# design.net
KiCad netlist of a schematic drawn in Altium Designer
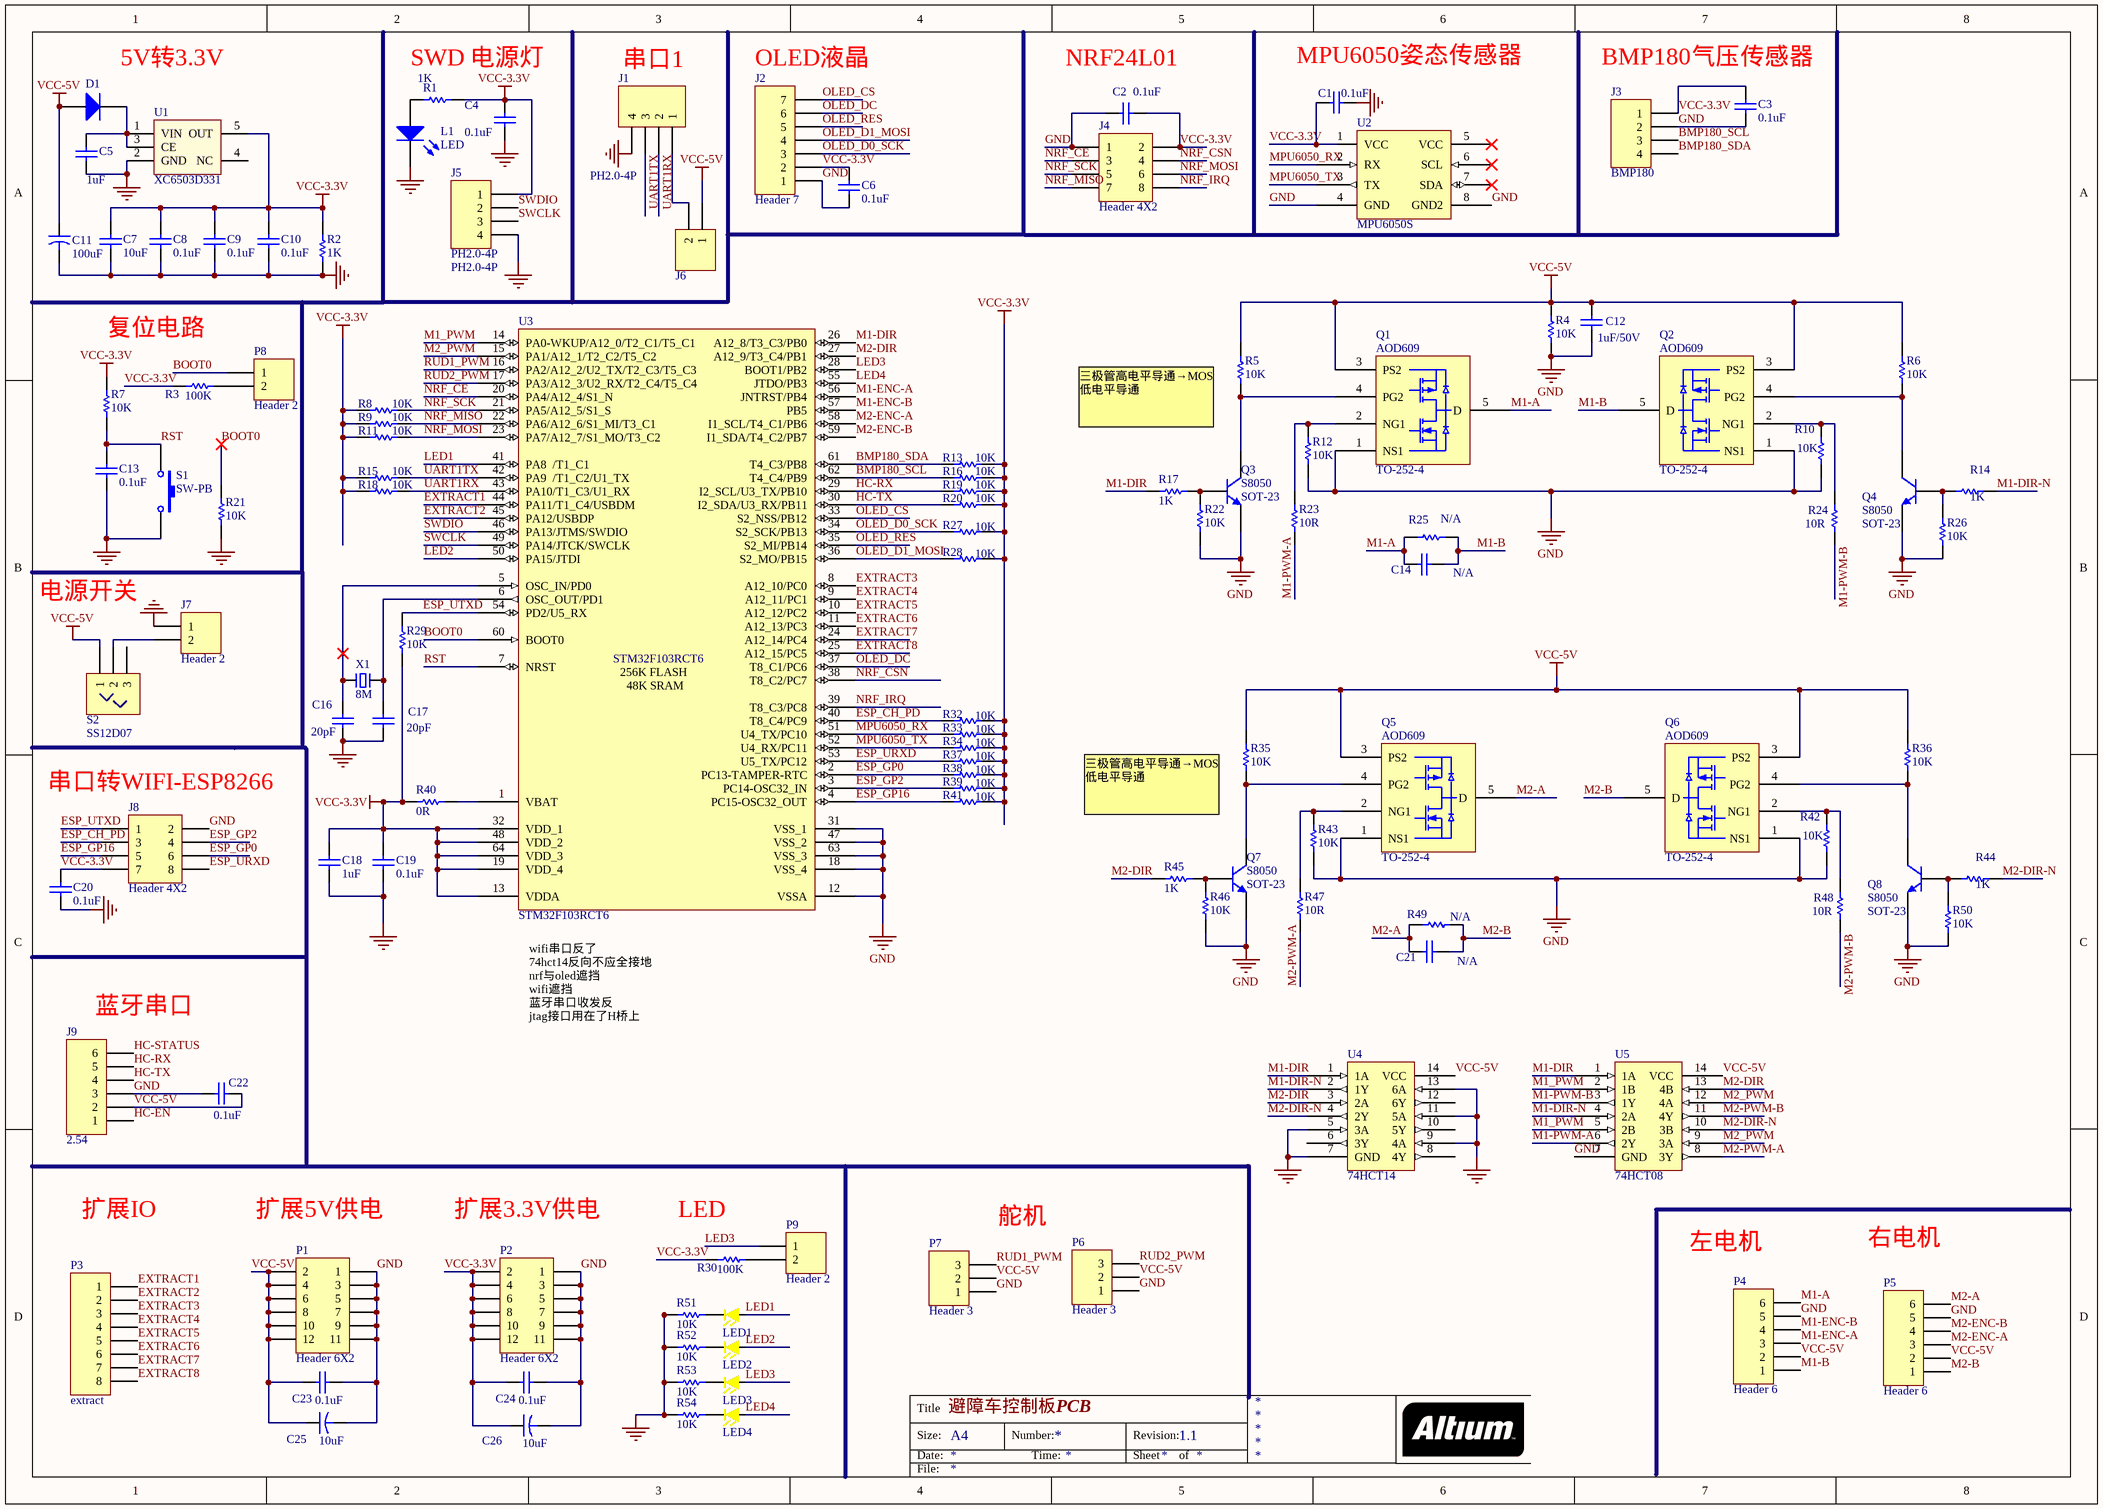
[diagram p0: 避障车控制板.SchDoc]

(export (version "E")
  (design (tool "Eeschema 10.0.6"))
  (components
    (comp (ref "C1")
      (value "0.1uF")
      (footprint "0805_LY")
      (description "Capacitor")
      (fields (field (name "PUBLISHER") "Altium Limited"))
      (libsource (lib "Miscellaneous Devices") (part "Cap"))
    )
    (comp (ref "C2")
      (value "0.1uF")
      (footprint "0805_LY")
      (description "Capacitor")
      (fields (field (name "PUBLISHER") "Altium Limited"))
      (libsource (lib "Miscellaneous Devices") (part "Cap"))
    )
    (comp (ref "C3")
      (value "0.1uF")
      (footprint "0805_LY")
      (description "电容0603")
      (fields (field (name "PUBLISHER") "Altium Limited"))
      (libsource (lib "Liyao原理图库") (part "Cap"))
    )
    (comp (ref "C4")
      (value "0.1uF")
      (footprint "0805_LY")
      (description "Capacitor")
      (fields (field (name "PUBLISHER") "Altium Limited"))
      (libsource (lib "Miscellaneous Devices") (part "Cap"))
    )
    (comp (ref "C5")
      (value "1uF")
      (footprint "0805_LY")
      (description "Capacitor")
      (fields (field (name "PUBLISHER") "Altium Limited"))
      (libsource (lib "Miscellaneous Devices") (part "Cap"))
    )
    (comp (ref "C6")
      (value "0.1uF")
      (footprint "0805_LY")
      (description "Capacitor")
      (fields (field (name "PUBLISHER") "Altium Limited"))
      (libsource (lib "Miscellaneous Devices") (part "Cap"))
    )
    (comp (ref "C7")
      (value "10uF")
      (footprint "0805_LY")
      (description "Capacitor")
      (fields (field (name "PUBLISHER") "Altium Limited"))
      (libsource (lib "Miscellaneous Devices") (part "Cap"))
    )
    (comp (ref "C8")
      (value "0.1uF")
      (footprint "0805_LY")
      (description "Capacitor")
      (fields (field (name "PUBLISHER") "Altium Limited"))
      (libsource (lib "Miscellaneous Devices") (part "Cap"))
    )
    (comp (ref "C9")
      (value "0.1uF")
      (footprint "0805_LY")
      (description "Capacitor")
      (fields (field (name "PUBLISHER") "Altium Limited"))
      (libsource (lib "Miscellaneous Devices") (part "Cap"))
    )
    (comp (ref "C10")
      (value "0.1uF")
      (footprint "0805_LY")
      (description "Capacitor")
      (fields (field (name "PUBLISHER") "Altium Limited"))
      (libsource (lib "Miscellaneous Devices") (part "Cap"))
    )
    (comp (ref "C11")
      (value "100uF")
      (footprint "TC6.3*7.7")
      (description "100uf/35v电解电容")
      (fields (field (name "PUBLISHER") "Altium Limited"))
      (libsource (lib "Liyao原理图库") (part "Cap100uf"))
    )
    (comp (ref "C12")
      (value "1uF/50V")
      (footprint "0805_LY")
      (description "Capacitor")
      (fields (field (name "PUBLISHER") "Altium Limited"))
      (libsource (lib "Miscellaneous Devices") (part "Cap"))
    )
    (comp (ref "C13")
      (value "0.1uF")
      (footprint "0805_LY")
      (description "Capacitor")
      (fields (field (name "PUBLISHER") "Altium Limited"))
      (libsource (lib "Miscellaneous Devices") (part "Cap"))
    )
    (comp (ref "C14")
      (value "N/A")
      (footprint "0805_LY")
      (description "Capacitor")
      (fields (field (name "PUBLISHER") "Altium Limited"))
      (libsource (lib "Miscellaneous Devices") (part "Cap"))
    )
    (comp (ref "C16")
      (value "20pF")
      (footprint "0805_LY")
      (description "Capacitor")
      (fields (field (name "PUBLISHER") "Altium Limited"))
      (libsource (lib "Miscellaneous Devices") (part "Cap"))
    )
    (comp (ref "C17")
      (value "20pF")
      (footprint "0805_LY")
      (description "Capacitor")
      (fields (field (name "PUBLISHER") "Altium Limited"))
      (libsource (lib "Miscellaneous Devices") (part "Cap"))
    )
    (comp (ref "C18")
      (value "1uF")
      (footprint "0805_LY")
      (description "Capacitor")
      (fields (field (name "PUBLISHER") "Altium Limited"))
      (libsource (lib "Miscellaneous Devices") (part "Cap"))
    )
    (comp (ref "C19")
      (value "0.1uF")
      (footprint "0805_LY")
      (description "Capacitor")
      (fields (field (name "PUBLISHER") "Altium Limited"))
      (libsource (lib "Miscellaneous Devices") (part "Cap"))
    )
    (comp (ref "C20")
      (value "0.1uF")
      (footprint "0805_LY")
      (description "Capacitor")
      (fields (field (name "PUBLISHER") "Altium Limited"))
      (libsource (lib "Miscellaneous Devices") (part "Cap"))
    )
    (comp (ref "C21")
      (value "N/A")
      (footprint "0805_LY")
      (description "Capacitor")
      (fields (field (name "PUBLISHER") "Altium Limited"))
      (libsource (lib "Miscellaneous Devices") (part "Cap"))
    )
    (comp (ref "C22")
      (value "0.1uF")
      (footprint "0805_LY")
      (description "Capacitor")
      (fields (field (name "PUBLISHER") "Altium Limited"))
      (libsource (lib "Miscellaneous Devices") (part "Cap"))
    )
    (comp (ref "C23")
      (value "0.1uF")
      (footprint "0805_LY")
      (description "电容0603")
      (fields (field (name "PUBLISHER") "Altium Limited"))
      (libsource (lib "Liyao原理图库") (part "Cap"))
    )
    (comp (ref "C24")
      (value "0.1uF")
      (footprint "0805_LY")
      (description "电容0603")
      (fields (field (name "PUBLISHER") "Altium Limited"))
      (libsource (lib "Liyao原理图库") (part "Cap"))
    )
    (comp (ref "C25")
      (value "10uF")
      (footprint "TC5*5")
      (description "10uf/35v电解电容")
      (fields (field (name "PUBLISHER") "Altium Limited"))
      (libsource (lib "Liyao原理图库") (part "Cap10uf"))
    )
    (comp (ref "C26")
      (value "10uF")
      (footprint "TC5*5")
      (description "10uf/35v电解电容")
      (fields (field (name "PUBLISHER") "Altium Limited"))
      (libsource (lib "Liyao原理图库") (part "Cap10uf"))
    )
    (comp (ref "D1")
      (value "SS14")
      (footprint "SMA")
      (description "28V 1A")
      (fields (field (name "PUBLISHER") "Altium Limited"))
      (libsource (lib "Liyao原理图库") (part "SS14"))
    )
    (comp (ref "J1")
      (value "PH2.0-4P")
      (footprint "XH2.54-4P")
      (description "插座XH2.54-4P")
      (fields (field (name "Comment") "XH2.54-4P") (field (name "PUBLISHER") "Altium Limited"))
      (libsource (lib "Liyao原理图库") (part "XH2.54-4P"))
    )
    (comp (ref "J2")
      (value "Header 7")
      (footprint "HDR1X7")
      (description "Header, 7-Pin")
      (fields (field (name "PUBLISHER") "Altium Limited"))
      (libsource (lib "Miscellaneous Connectors") (part "Header 7"))
    )
    (comp (ref "J3")
      (value "BMP180")
      (footprint "HDR1X4")
      (description "Header, 4-Pin")
      (fields (field (name "Comment") "PH2.0-4P") (field (name "PUBLISHER") "Altium Limited"))
      (libsource (lib "Miscellaneous Connectors") (part "Header 4"))
    )
    (comp (ref "J4")
      (value "Header 4X2")
      (footprint "HDR2X4")
      (description "Header, 4-Pin, Dual row")
      (fields (field (name "PUBLISHER") "Altium Limited"))
      (libsource (lib "Miscellaneous Connectors") (part "Header 4X2"))
    )
    (comp (ref "J5")
      (value "PH2.0-4P")
      (footprint "PH2.0-4P")
      (description "Header, 4-Pin")
      (fields (field (name "ALTIUM_VALUE") "PH2.0-4P") (field (name "PUBLISHER") "Altium Limited"))
      (libsource (lib "Miscellaneous Connectors") (part "Header 4"))
    )
    (comp (ref "J6")
      (value "XH2.54-2P")
      (footprint "CAP2.54-2P")
      (description "插座XH2.54-2P")
      (fields (field (name "PUBLISHER") "Altium Limited"))
      (libsource (lib "Liyao原理图库") (part "XH2.54-2P"))
    )
    (comp (ref "J7")
      (value "Header 2")
      (footprint "XH2.54-2P")
      (description "Header, 2-Pin")
      (fields (field (name "PUBLISHER") "Altium Limited"))
      (libsource (lib "Miscellaneous Connectors") (part "Header 2"))
    )
    (comp (ref "J8")
      (value "Header 4X2")
      (footprint "HDR2X4")
      (description "Header, 4-Pin, Dual row")
      (fields (field (name "PUBLISHER") "Altium Limited"))
      (libsource (lib "Miscellaneous Connectors") (part "Header 4X2"))
    )
    (comp (ref "J9")
      (value "2.54")
      (footprint "HDR1X6")
      (description "Header, 6-Pin")
      (fields (field (name "PUBLISHER") "Altium Limited"))
      (libsource (lib "Liyao端子库") (part "Header 6"))
    )
    (comp (ref "L1") (value "LED") (footprint "0805_LED") (libsource (lib "Sparks") (part "LED")))
    (comp (ref "LED1")
      (value "LED-Y")
      (footprint "0805_LED")
      (description "LED黄0603")
      (libsource (lib "Liyao原理图库") (part "LED-Y"))
    )
    (comp (ref "LED2")
      (value "LED-Y")
      (footprint "0805_LED")
      (description "LED黄0603")
      (libsource (lib "Liyao原理图库") (part "LED-Y"))
    )
    (comp (ref "LED3")
      (value "LED-Y")
      (footprint "0805_LED")
      (description "LED黄0603")
      (libsource (lib "Liyao原理图库") (part "LED-Y"))
    )
    (comp (ref "LED4")
      (value "LED-Y")
      (footprint "0805_LED")
      (description "LED黄0603")
      (libsource (lib "Liyao原理图库") (part "LED-Y"))
    )
    (comp (ref "P1")
      (value "Header 6X2")
      (footprint "HDR2X6")
      (description "Header, 6-Pin, Dual row")
      (fields (field (name "PUBLISHER") "Altium Limited"))
      (libsource (lib "Miscellaneous Connectors") (part "Header 6X2"))
    )
    (comp (ref "P2")
      (value "Header 6X2")
      (footprint "HDR2X6")
      (description "Header, 6-Pin, Dual row")
      (fields (field (name "PUBLISHER") "Altium Limited"))
      (libsource (lib "Miscellaneous Connectors") (part "Header 6X2"))
    )
    (comp (ref "P3")
      (value "extract")
      (footprint "HDR1X8")
      (description "Header, 8-Pin")
      (fields (field (name "PUBLISHER") "Altium Limited"))
      (libsource (lib "Miscellaneous Connectors") (part "Header 8"))
    )
    (comp (ref "P4")
      (value "Header 6")
      (footprint "PH2.0-6p")
      (description "Header, 6-Pin")
      (fields (field (name "PUBLISHER") "Altium Limited"))
      (libsource (lib "Miscellaneous Connectors") (part "Header 6"))
    )
    (comp (ref "P5")
      (value "Header 6")
      (footprint "PH2.0-6p")
      (description "Header, 6-Pin")
      (fields (field (name "PUBLISHER") "Altium Limited"))
      (libsource (lib "Miscellaneous Connectors") (part "Header 6"))
    )
    (comp (ref "P6")
      (value "Header 3")
      (footprint "HDR1X3")
      (description "Header, 3-Pin")
      (fields (field (name "PUBLISHER") "Altium Limited"))
      (libsource (lib "Miscellaneous Connectors") (part "Header 3"))
    )
    (comp (ref "P7")
      (value "Header 3")
      (footprint "HDR1X3")
      (description "Header, 3-Pin")
      (fields (field (name "PUBLISHER") "Altium Limited"))
      (libsource (lib "Miscellaneous Connectors") (part "Header 3"))
    )
    (comp (ref "P8")
      (value "Header 2")
      (footprint "HDR1X2")
      (description "Header, 2-Pin")
      (fields (field (name "PUBLISHER") "Altium Limited"))
      (libsource (lib "Liyao端子库") (part "Header 2"))
    )
    (comp (ref "P9")
      (value "Header 2")
      (footprint "HDR1X2")
      (description "Header, 2-Pin")
      (fields (field (name "PUBLISHER") "Altium Limited"))
      (libsource (lib "Liyao端子库") (part "Header 2"))
    )
    (comp (ref "Q1")
      (value "TO-252-4")
      (footprint "TO-252-4L")
      (fields (field (name "ALTIUM_VALUE") "AOD609"))
      (libsource (lib "CYSchlib") (part "MOS-DUAL-N/P"))
    )
    (comp (ref "Q2")
      (value "TO-252-4")
      (footprint "TO-252-4L")
      (fields (field (name "ALTIUM_VALUE") "AOD609"))
      (libsource (lib "") (part "MOS-DUAL-N/P_1"))
    )
    (comp (ref "Q3")
      (value "SOT-23")
      (footprint "SOT-23_L")
      (description "NPN Bipolar Transistor")
      (fields (field (name "ALTIUM_VALUE") "S8050") (field (name "PUBLISHER") "Altium Limited"))
      (libsource (lib "CYSchlib") (part "NPN"))
    )
    (comp (ref "Q4")
      (value "SOT-23")
      (footprint "SOT-23_L")
      (description "NPN Bipolar Transistor")
      (fields (field (name "ALTIUM_VALUE") "S8050") (field (name "PUBLISHER") "Altium Limited"))
      (libsource (lib "CYSchlib") (part "NPN"))
    )
    (comp (ref "Q5")
      (value "TO-252-4")
      (footprint "TO-252-4L")
      (fields (field (name "ALTIUM_VALUE") "AOD609"))
      (libsource (lib "CYSchlib") (part "MOS-DUAL-N/P"))
    )
    (comp (ref "Q6")
      (value "TO-252-4")
      (footprint "TO-252-4L")
      (fields (field (name "ALTIUM_VALUE") "AOD609"))
      (libsource (lib "") (part "MOS-DUAL-N/P_1"))
    )
    (comp (ref "Q7")
      (value "SOT-23")
      (footprint "SOT-23_L")
      (description "NPN Bipolar Transistor")
      (fields (field (name "ALTIUM_VALUE") "S8050") (field (name "PUBLISHER") "Altium Limited"))
      (libsource (lib "CYSchlib") (part "NPN"))
    )
    (comp (ref "Q8")
      (value "SOT-23")
      (footprint "SOT-23_L")
      (description "NPN Bipolar Transistor")
      (fields (field (name "ALTIUM_VALUE") "S8050") (field (name "PUBLISHER") "Altium Limited"))
      (libsource (lib "CYSchlib") (part "NPN"))
    )
    (comp (ref "R1")
      (value "1K")
      (footprint "0805_LY")
      (description "Resistor")
      (fields (field (name "PUBLISHER") "Altium Limited"))
      (libsource (lib "Miscellaneous Devices") (part "Res1"))
    )
    (comp (ref "R2")
      (value "1K")
      (footprint "0805_LY")
      (description "Resistor")
      (fields (field (name "PUBLISHER") "Altium Limited"))
      (libsource (lib "Miscellaneous Devices") (part "Res1"))
    )
    (comp (ref "R3")
      (value "100K")
      (footprint "6-0805_N")
      (description "电阻0603")
      (fields (field (name "PUBLISHER") "Altium Limited"))
      (libsource (lib "Liyao原理图库") (part "Res"))
    )
    (comp (ref "R4")
      (value "10K")
      (footprint "0805_LY")
      (description "Resistor")
      (fields (field (name "PUBLISHER") "Altium Limited"))
      (libsource (lib "Miscellaneous Devices") (part "Res1"))
    )
    (comp (ref "R5")
      (value "10K")
      (footprint "0805_LY")
      (description "Resistor")
      (fields (field (name "PUBLISHER") "Altium Limited"))
      (libsource (lib "Miscellaneous Devices") (part "Res1"))
    )
    (comp (ref "R6")
      (value "10K")
      (footprint "0805_LY")
      (description "Resistor")
      (fields (field (name "PUBLISHER") "Altium Limited"))
      (libsource (lib "Miscellaneous Devices") (part "Res1"))
    )
    (comp (ref "R7")
      (value "10K")
      (footprint "0805_LY")
      (description "Resistor")
      (fields (field (name "PUBLISHER") "Altium Limited"))
      (libsource (lib "Miscellaneous Devices") (part "Res1"))
    )
    (comp (ref "R8")
      (value "10K")
      (footprint "0805_LY")
      (description "电阻0603")
      (fields (field (name "PUBLISHER") "Altium Limited"))
      (libsource (lib "Liyao原理图库") (part "Res"))
    )
    (comp (ref "R9")
      (value "10K")
      (footprint "0805_LY")
      (description "电阻0603")
      (fields (field (name "PUBLISHER") "Altium Limited"))
      (libsource (lib "Liyao原理图库") (part "Res"))
    )
    (comp (ref "R10")
      (value "10K")
      (footprint "0805_LY")
      (description "Resistor")
      (fields (field (name "PUBLISHER") "Altium Limited"))
      (libsource (lib "Miscellaneous Devices") (part "Res1"))
    )
    (comp (ref "R11")
      (value "10K")
      (footprint "6-0805_N")
      (description "电阻0603")
      (fields (field (name "PUBLISHER") "Altium Limited"))
      (libsource (lib "Liyao原理图库") (part "Res"))
    )
    (comp (ref "R12")
      (value "10K")
      (footprint "0805_LY")
      (description "Resistor")
      (fields (field (name "PUBLISHER") "Altium Limited"))
      (libsource (lib "Miscellaneous Devices") (part "Res1"))
    )
    (comp (ref "R13")
      (value "10K")
      (footprint "0805_LY")
      (description "电阻0603")
      (fields (field (name "PUBLISHER") "Altium Limited"))
      (libsource (lib "Liyao原理图库") (part "Res"))
    )
    (comp (ref "R14")
      (value "1K")
      (footprint "0805_LY")
      (description "Resistor")
      (fields (field (name "PUBLISHER") "Altium Limited"))
      (libsource (lib "Miscellaneous Devices") (part "Res1"))
    )
    (comp (ref "R15")
      (value "10K")
      (footprint "0805_LY")
      (description "电阻0603")
      (fields (field (name "PUBLISHER") "Altium Limited"))
      (libsource (lib "Liyao原理图库") (part "Res"))
    )
    (comp (ref "R16")
      (value "10K")
      (footprint "0805_LY")
      (description "电阻0603")
      (fields (field (name "PUBLISHER") "Altium Limited"))
      (libsource (lib "Liyao原理图库") (part "Res"))
    )
    (comp (ref "R17")
      (value "1K")
      (footprint "0805_LY")
      (description "Resistor")
      (fields (field (name "PUBLISHER") "Altium Limited"))
      (libsource (lib "Miscellaneous Devices") (part "Res1"))
    )
    (comp (ref "R18")
      (value "10K")
      (footprint "0805_LY")
      (description "电阻0603")
      (fields (field (name "PUBLISHER") "Altium Limited"))
      (libsource (lib "Liyao原理图库") (part "Res"))
    )
    (comp (ref "R19")
      (value "10K")
      (footprint "0805_LY")
      (description "电阻0603")
      (fields (field (name "PUBLISHER") "Altium Limited"))
      (libsource (lib "Liyao原理图库") (part "Res"))
    )
    (comp (ref "R20")
      (value "10K")
      (footprint "0805_LY")
      (description "电阻0603")
      (fields (field (name "PUBLISHER") "Altium Limited"))
      (libsource (lib "Liyao原理图库") (part "Res"))
    )
    (comp (ref "R21")
      (value "10K")
      (footprint "0805_LY")
      (description "Resistor")
      (fields (field (name "PUBLISHER") "Altium Limited"))
      (libsource (lib "Miscellaneous Devices") (part "Res1"))
    )
    (comp (ref "R22")
      (value "10K")
      (footprint "0805_LY")
      (description "Resistor")
      (fields (field (name "PUBLISHER") "Altium Limited"))
      (libsource (lib "Miscellaneous Devices") (part "Res1"))
    )
    (comp (ref "R23")
      (value "10R")
      (footprint "0805_LY")
      (description "Resistor")
      (fields (field (name "PUBLISHER") "Altium Limited"))
      (libsource (lib "Miscellaneous Devices") (part "Res1"))
    )
    (comp (ref "R24")
      (value "10R")
      (footprint "0805_LY")
      (description "Resistor")
      (fields (field (name "PUBLISHER") "Altium Limited"))
      (libsource (lib "Miscellaneous Devices") (part "Res1"))
    )
    (comp (ref "R25")
      (value "N/A")
      (footprint "0805_LY")
      (description "Resistor")
      (fields (field (name "PUBLISHER") "Altium Limited"))
      (libsource (lib "Miscellaneous Devices") (part "Res1"))
    )
    (comp (ref "R26")
      (value "10K")
      (footprint "0805_LY")
      (description "Resistor")
      (fields (field (name "PUBLISHER") "Altium Limited"))
      (libsource (lib "Miscellaneous Devices") (part "Res1"))
    )
    (comp (ref "R27")
      (value "10K")
      (footprint "0805_LY")
      (description "电阻0603")
      (fields (field (name "PUBLISHER") "Altium Limited"))
      (libsource (lib "Liyao原理图库") (part "Res"))
    )
    (comp (ref "R28")
      (value "10K")
      (footprint "0805_LY")
      (description "电阻0603")
      (fields (field (name "PUBLISHER") "Altium Limited"))
      (libsource (lib "Liyao原理图库") (part "Res"))
    )
    (comp (ref "R29")
      (value "10K")
      (footprint "0805_LY")
      (description "电阻0603")
      (fields (field (name "PUBLISHER") "Altium Limited"))
      (libsource (lib "Liyao原理图库") (part "Res"))
    )
    (comp (ref "R30")
      (value "100K")
      (footprint "6-0805_N")
      (description "电阻0603")
      (fields (field (name "PUBLISHER") "Altium Limited"))
      (libsource (lib "Liyao原理图库") (part "Res"))
    )
    (comp (ref "R32")
      (value "10K")
      (footprint "0805_LY")
      (description "电阻0603")
      (fields (field (name "PUBLISHER") "Altium Limited"))
      (libsource (lib "Liyao原理图库") (part "Res"))
    )
    (comp (ref "R33")
      (value "10K")
      (footprint "0805_LY")
      (description "电阻0603")
      (fields (field (name "PUBLISHER") "Altium Limited"))
      (libsource (lib "Liyao原理图库") (part "Res"))
    )
    (comp (ref "R34")
      (value "10K")
      (footprint "0805_LY")
      (description "电阻0603")
      (fields (field (name "PUBLISHER") "Altium Limited"))
      (libsource (lib "Liyao原理图库") (part "Res"))
    )
    (comp (ref "R35")
      (value "10K")
      (footprint "0805_LY")
      (description "Resistor")
      (fields (field (name "PUBLISHER") "Altium Limited"))
      (libsource (lib "Miscellaneous Devices") (part "Res1"))
    )
    (comp (ref "R36")
      (value "10K")
      (footprint "0805_LY")
      (description "Resistor")
      (fields (field (name "PUBLISHER") "Altium Limited"))
      (libsource (lib "Miscellaneous Devices") (part "Res1"))
    )
    (comp (ref "R37")
      (value "10K")
      (footprint "0805_LY")
      (description "电阻0603")
      (fields (field (name "PUBLISHER") "Altium Limited"))
      (libsource (lib "Liyao原理图库") (part "Res"))
    )
    (comp (ref "R38")
      (value "10K")
      (footprint "0805_LY")
      (description "电阻0603")
      (fields (field (name "PUBLISHER") "Altium Limited"))
      (libsource (lib "Liyao原理图库") (part "Res"))
    )
    (comp (ref "R39")
      (value "10K")
      (footprint "0805_LY")
      (description "电阻0603")
      (fields (field (name "PUBLISHER") "Altium Limited"))
      (libsource (lib "Liyao原理图库") (part "Res"))
    )
    (comp (ref "R40")
      (value "0R")
      (footprint "0805_LY")
      (description "Resistor")
      (fields (field (name "PUBLISHER") "Altium Limited"))
      (libsource (lib "Miscellaneous Devices") (part "Res1"))
    )
    (comp (ref "R41")
      (value "10K")
      (footprint "0805_LY")
      (description "电阻0603")
      (fields (field (name "PUBLISHER") "Altium Limited"))
      (libsource (lib "Liyao原理图库") (part "Res"))
    )
    (comp (ref "R42")
      (value "10K")
      (footprint "0805_LY")
      (description "Resistor")
      (fields (field (name "PUBLISHER") "Altium Limited"))
      (libsource (lib "Miscellaneous Devices") (part "Res1"))
    )
    (comp (ref "R43")
      (value "10K")
      (footprint "0805_LY")
      (description "Resistor")
      (fields (field (name "PUBLISHER") "Altium Limited"))
      (libsource (lib "Miscellaneous Devices") (part "Res1"))
    )
    (comp (ref "R44")
      (value "1K")
      (footprint "0805_LY")
      (description "Resistor")
      (fields (field (name "PUBLISHER") "Altium Limited"))
      (libsource (lib "Miscellaneous Devices") (part "Res1"))
    )
    (comp (ref "R45")
      (value "1K")
      (footprint "0805_LY")
      (description "Resistor")
      (fields (field (name "PUBLISHER") "Altium Limited"))
      (libsource (lib "Miscellaneous Devices") (part "Res1"))
    )
    (comp (ref "R46")
      (value "10K")
      (footprint "0805_LY")
      (description "Resistor")
      (fields (field (name "PUBLISHER") "Altium Limited"))
      (libsource (lib "Miscellaneous Devices") (part "Res1"))
    )
    (comp (ref "R47")
      (value "10R")
      (footprint "0805_LY")
      (description "Resistor")
      (fields (field (name "PUBLISHER") "Altium Limited"))
      (libsource (lib "Miscellaneous Devices") (part "Res1"))
    )
    (comp (ref "R48")
      (value "10R")
      (footprint "0805_LY")
      (description "Resistor")
      (fields (field (name "PUBLISHER") "Altium Limited"))
      (libsource (lib "Miscellaneous Devices") (part "Res1"))
    )
    (comp (ref "R49")
      (value "N/A")
      (footprint "0805_LY")
      (description "Resistor")
      (fields (field (name "PUBLISHER") "Altium Limited"))
      (libsource (lib "Miscellaneous Devices") (part "Res1"))
    )
    (comp (ref "R50")
      (value "10K")
      (footprint "0805_LY")
      (description "Resistor")
      (fields (field (name "PUBLISHER") "Altium Limited"))
      (libsource (lib "Miscellaneous Devices") (part "Res1"))
    )
    (comp (ref "R51")
      (value "10K")
      (footprint "0805_LY")
      (description "电阻0603")
      (fields (field (name "PUBLISHER") "Altium Limited"))
      (libsource (lib "Liyao原理图库") (part "Res"))
    )
    (comp (ref "R52")
      (value "10K")
      (footprint "0805_LY")
      (description "电阻0603")
      (fields (field (name "PUBLISHER") "Altium Limited"))
      (libsource (lib "Liyao原理图库") (part "Res"))
    )
    (comp (ref "R53")
      (value "10K")
      (footprint "0805_LY")
      (description "电阻0603")
      (fields (field (name "PUBLISHER") "Altium Limited"))
      (libsource (lib "Liyao原理图库") (part "Res"))
    )
    (comp (ref "R54")
      (value "10K")
      (footprint "0805_LY")
      (description "电阻0603")
      (fields (field (name "PUBLISHER") "Altium Limited"))
      (libsource (lib "Liyao原理图库") (part "Res"))
    )
    (comp (ref "S1")
      (value "SW-PB")
      (footprint "SW-KEY")
      (description "Switch")
      (fields (field (name "PUBLISHER") "Altium Limited"))
      (libsource (lib "Miscellaneous Devices") (part "SW-PB"))
    )
    (comp (ref "S2") (value "SS12D07") (footprint "SS-12D07") (libsource (lib "Liyao原理图库") (part "SS12D07")))
    (comp (ref "U1")
      (value "XC6503D331")
      (footprint "SOT23-5")
      (libsource (lib "CYSchlib") (part "XC6503Dxxx"))
    )
    (comp (ref "U2")
      (value "MPU6050S")
      (footprint "MPU6050S")
      (libsource (lib "Liyao原理图库") (part "MPU6050S"))
    )
    (comp (ref "U3")
      (value "STM32F103RCT6")
      (footprint "LQFP64_N")
      (description "256K Flash 48K RAM")
      (fields (field (name "PUBLISHER") "Altium Limited"))
      (libsource (lib "Liyao原理图库") (part "STM32F103RCT6"))
    )
    (comp (ref "U4")
      (value "74HCT14")
      (footprint "SO-14")
      (description "反向输出 AL-YH,AH-YL")
      (libsource (lib "Liyao原理图库") (part "74HCT14"))
    )
    (comp (ref "U5")
      (value "74HCT08")
      (footprint "SO-14")
      (description "与门AH&&BH?YH:YL")
      (libsource (lib "Liyao原理图库") (part "74HCT08"))
    )
    (comp (ref "X1") (value "8M") (footprint "HC-49SMD") (libsource (lib "CYSchlib") (part "XTAL")))
  )
  (nets
    (net (code "1") (name "/BMP180_SCL") (class "Default")
      (node (ref "J3") (pin "3") (pinfunction "3_3") (pintype "passive"))
      (node (ref "R16") (pin "1") (pinfunction "1_1") (pintype "passive"))
      (node (ref "U3") (pin "62") (pinfunction "T4_C4/PB9_62") (pintype "bidirectional"))
    )
    (net (code "2") (name "/BMP180_SDA") (class "Default")
      (node (ref "J3") (pin "4") (pinfunction "4_4") (pintype "passive"))
      (node (ref "R13") (pin "1") (pinfunction "1_1") (pintype "passive"))
      (node (ref "U3") (pin "61") (pinfunction "T4_C3/PB8_61") (pintype "bidirectional"))
    )
    (net (code "3") (name "/BOOT0") (class "Default")
      (node (ref "P8") (pin "1") (pinfunction "1_1") (pintype "passive"))
      (node (ref "R21") (pin "1") (pinfunction "1_1") (pintype "passive"))
      (node (ref "U3") (pin "60") (pinfunction "BOOT0_60") (pintype "input"))
    )
    (net (code "4") (name "/ESP_CH_PD") (class "Default")
      (node (ref "J8") (pin "3") (pinfunction "3_3") (pintype "passive"))
      (node (ref "R32") (pin "1") (pinfunction "1_1") (pintype "passive"))
      (node (ref "U3") (pin "40") (pinfunction "T8_C4/PC9_40") (pintype "bidirectional"))
    )
    (net (code "5") (name "/ESP_GP0") (class "Default")
      (node (ref "J8") (pin "6") (pinfunction "6_6") (pintype "passive"))
      (node (ref "R38") (pin "1") (pinfunction "1_1") (pintype "passive"))
      (node (ref "U3") (pin "2") (pinfunction "PC13-TAMPER-RTC_2") (pintype "bidirectional"))
    )
    (net (code "6") (name "/ESP_GP2") (class "Default")
      (node (ref "J8") (pin "4") (pinfunction "4_4") (pintype "passive"))
      (node (ref "R39") (pin "1") (pinfunction "1_1") (pintype "passive"))
      (node (ref "U3") (pin "3") (pinfunction "PC14-OSC32_IN_3") (pintype "bidirectional"))
    )
    (net (code "7") (name "/ESP_GP16") (class "Default")
      (node (ref "J8") (pin "5") (pinfunction "5_5") (pintype "passive"))
      (node (ref "R41") (pin "1") (pinfunction "1_1") (pintype "passive"))
      (node (ref "U3") (pin "4") (pinfunction "PC15-OSC32_OUT_4") (pintype "bidirectional"))
    )
    (net (code "8") (name "/ESP_URXD") (class "Default")
      (node (ref "J8") (pin "8") (pinfunction "8_8") (pintype "passive"))
      (node (ref "R37") (pin "1") (pinfunction "1_1") (pintype "passive"))
      (node (ref "U3") (pin "53") (pinfunction "U5_TX/PC12_53") (pintype "bidirectional"))
    )
    (net (code "9") (name "/ESP_UTXD") (class "Default")
      (node (ref "J8") (pin "1") (pinfunction "1_1") (pintype "passive"))
      (node (ref "R29") (pin "2") (pinfunction "2_2") (pintype "passive"))
      (node (ref "U3") (pin "54") (pinfunction "PD2/U5_RX_54") (pintype "bidirectional"))
    )
    (net (code "10") (name "/EXTRACT1") (class "Default")
      (node (ref "P3") (pin "1") (pinfunction "1_1") (pintype "passive"))
      (node (ref "U3") (pin "44") (pinfunction "PA11/T1_C4/USBDM_44") (pintype "bidirectional"))
    )
    (net (code "11") (name "/EXTRACT2") (class "Default")
      (node (ref "P3") (pin "2") (pinfunction "2_2") (pintype "passive"))
      (node (ref "U3") (pin "45") (pinfunction "PA12/USBDP_45") (pintype "bidirectional"))
    )
    (net (code "12") (name "/EXTRACT3") (class "Default")
      (node (ref "P3") (pin "3") (pinfunction "3_3") (pintype "passive"))
      (node (ref "U3") (pin "8") (pinfunction "A12_10/PC0_8") (pintype "bidirectional"))
    )
    (net (code "13") (name "/EXTRACT4") (class "Default")
      (node (ref "P3") (pin "4") (pinfunction "4_4") (pintype "passive"))
      (node (ref "U3") (pin "9") (pinfunction "A12_11/PC1_9") (pintype "bidirectional"))
    )
    (net (code "14") (name "/EXTRACT5") (class "Default")
      (node (ref "P3") (pin "5") (pinfunction "5_5") (pintype "passive"))
      (node (ref "U3") (pin "10") (pinfunction "A12_12/PC2_10") (pintype "bidirectional"))
    )
    (net (code "15") (name "/EXTRACT6") (class "Default")
      (node (ref "P3") (pin "6") (pinfunction "6_6") (pintype "passive"))
      (node (ref "U3") (pin "11") (pinfunction "A12_13/PC3_11") (pintype "bidirectional"))
    )
    (net (code "16") (name "/EXTRACT7") (class "Default")
      (node (ref "P3") (pin "7") (pinfunction "7_7") (pintype "passive"))
      (node (ref "U3") (pin "24") (pinfunction "A12_14/PC4_24") (pintype "bidirectional"))
    )
    (net (code "17") (name "/EXTRACT8") (class "Default")
      (node (ref "P3") (pin "8") (pinfunction "8_8") (pintype "passive"))
      (node (ref "U3") (pin "25") (pinfunction "A12_15/PC5_25") (pintype "bidirectional"))
    )
    (net (code "18") (name "/HC-EN") (class "Default")
      (node (ref "J9") (pin "1") (pinfunction "1_1") (pintype "passive"))
    )
    (net (code "19") (name "/HC-RX") (class "Default")
      (node (ref "J9") (pin "5") (pinfunction "5_5") (pintype "passive"))
      (node (ref "R19") (pin "1") (pinfunction "1_1") (pintype "passive"))
      (node (ref "U3") (pin "29") (pinfunction "I2_SCL/U3_TX/PB10_29") (pintype "bidirectional"))
    )
    (net (code "20") (name "/HC-STATUS") (class "Default")
      (node (ref "J9") (pin "6") (pinfunction "6_6") (pintype "passive"))
    )
    (net (code "21") (name "/HC-TX") (class "Default")
      (node (ref "J9") (pin "4") (pinfunction "4_4") (pintype "passive"))
      (node (ref "R20") (pin "1") (pinfunction "1_1") (pintype "passive"))
      (node (ref "U3") (pin "30") (pinfunction "I2_SDA/U3_RX/PB11_30") (pintype "bidirectional"))
    )
    (net (code "22") (name "/LED1") (class "Default")
      (node (ref "LED1") (pin "1") (pinfunction "1_1") (pintype "passive"))
      (node (ref "U3") (pin "41") (pinfunction "PA8__/T1_C1_41") (pintype "bidirectional"))
    )
    (net (code "23") (name "/LED2") (class "Default")
      (node (ref "LED2") (pin "1") (pinfunction "1_1") (pintype "passive"))
      (node (ref "U3") (pin "50") (pinfunction "PA15/JTDI_50") (pintype "bidirectional"))
    )
    (net (code "24") (name "/LED3") (class "Default")
      (node (ref "LED3") (pin "1") (pinfunction "1_1") (pintype "passive"))
      (node (ref "P9") (pin "1") (pinfunction "1_1") (pintype "passive"))
      (node (ref "U3") (pin "28") (pinfunction "BOOT1/PB2_28") (pintype "bidirectional"))
    )
    (net (code "25") (name "/LED4") (class "Default")
      (node (ref "LED4") (pin "1") (pinfunction "1_1") (pintype "passive"))
      (node (ref "U3") (pin "55") (pinfunction "JTDO/PB3_55") (pintype "bidirectional"))
    )
    (net (code "26") (name "/M1-A") (class "Default")
      (node (ref "C14") (pin "2") (pinfunction "2_2") (pintype "passive"))
      (node (ref "P4") (pin "6") (pinfunction "6_6") (pintype "passive"))
      (node (ref "Q1") (pin "5") (pinfunction "D_5") (pintype "passive"))
      (node (ref "R25") (pin "2") (pinfunction "2_2") (pintype "passive"))
    )
    (net (code "27") (name "/M1-B") (class "Default")
      (node (ref "C14") (pin "1") (pinfunction "1_1") (pintype "passive"))
      (node (ref "P4") (pin "1") (pinfunction "1_1") (pintype "passive"))
      (node (ref "Q2") (pin "5") (pinfunction "D_5") (pintype "passive"))
      (node (ref "R25") (pin "1") (pinfunction "1_1") (pintype "passive"))
    )
    (net (code "28") (name "/M1-DIR") (class "Default")
      (node (ref "R17") (pin "2") (pinfunction "2_2") (pintype "passive"))
      (node (ref "U3") (pin "26") (pinfunction "A12_8/T3_C3/PB0_26") (pintype "bidirectional"))
      (node (ref "U4") (pin "1") (pinfunction "1A_1") (pintype "input"))
      (node (ref "U5") (pin "1") (pinfunction "1A_1") (pintype "input"))
    )
    (net (code "29") (name "/M1-DIR-N") (class "Default")
      (node (ref "R14") (pin "1") (pinfunction "1_1") (pintype "passive"))
      (node (ref "U4") (pin "2") (pinfunction "1Y_2") (pintype "output"))
      (node (ref "U5") (pin "4") (pinfunction "2A_4") (pintype "input"))
    )
    (net (code "30") (name "/M1-ENC-A") (class "Default")
      (node (ref "P4") (pin "3") (pinfunction "3_3") (pintype "passive"))
      (node (ref "U3") (pin "56") (pinfunction "JNTRST/PB4_56") (pintype "bidirectional"))
    )
    (net (code "31") (name "/M1-ENC-B") (class "Default")
      (node (ref "P4") (pin "4") (pinfunction "4_4") (pintype "passive"))
      (node (ref "U3") (pin "57") (pinfunction "PB5_57") (pintype "bidirectional"))
    )
    (net (code "32") (name "/M1-PWM-A") (class "Default")
      (node (ref "R23") (pin "2") (pinfunction "2_2") (pintype "passive"))
      (node (ref "U5") (pin "6") (pinfunction "2Y_6") (pintype "output"))
    )
    (net (code "33") (name "/M1-PWM-B") (class "Default")
      (node (ref "R24") (pin "2") (pinfunction "2_2") (pintype "passive"))
      (node (ref "U5") (pin "3") (pinfunction "1Y_3") (pintype "output"))
    )
    (net (code "34") (name "/M1_PWM") (class "Default")
      (node (ref "U3") (pin "14") (pinfunction "PA0-WKUP/A12_0/T2_C1/T5_C1_14") (pintype "bidirectional"))
      (node (ref "U5") (pin "2") (pinfunction "1B_2") (pintype "input"))
      (node (ref "U5") (pin "5") (pinfunction "2B_5") (pintype "input"))
    )
    (net (code "35") (name "/M2-A") (class "Default")
      (node (ref "C21") (pin "2") (pinfunction "2_2") (pintype "passive"))
      (node (ref "P5") (pin "6") (pinfunction "6_6") (pintype "passive"))
      (node (ref "Q5") (pin "5") (pinfunction "D_5") (pintype "passive"))
      (node (ref "R49") (pin "2") (pinfunction "2_2") (pintype "passive"))
    )
    (net (code "36") (name "/M2-B") (class "Default")
      (node (ref "C21") (pin "1") (pinfunction "1_1") (pintype "passive"))
      (node (ref "P5") (pin "1") (pinfunction "1_1") (pintype "passive"))
      (node (ref "Q6") (pin "5") (pinfunction "D_5") (pintype "passive"))
      (node (ref "R49") (pin "1") (pinfunction "1_1") (pintype "passive"))
    )
    (net (code "37") (name "/M2-DIR") (class "Default")
      (node (ref "R45") (pin "2") (pinfunction "2_2") (pintype "passive"))
      (node (ref "U3") (pin "27") (pinfunction "A12_9/T3_C4/PB1_27") (pintype "bidirectional"))
      (node (ref "U4") (pin "3") (pinfunction "2A_3") (pintype "input"))
      (node (ref "U5") (pin "13") (pinfunction "4B_13") (pintype "input"))
    )
    (net (code "38") (name "/M2-DIR-N") (class "Default")
      (node (ref "R44") (pin "1") (pinfunction "1_1") (pintype "passive"))
      (node (ref "U4") (pin "4") (pinfunction "2Y_4") (pintype "output"))
      (node (ref "U5") (pin "10") (pinfunction "3B_10") (pintype "input"))
    )
    (net (code "39") (name "/M2-ENC-A") (class "Default")
      (node (ref "P5") (pin "3") (pinfunction "3_3") (pintype "passive"))
      (node (ref "U3") (pin "58") (pinfunction "I1_SCL/T4_C1/PB6_58") (pintype "bidirectional"))
    )
    (net (code "40") (name "/M2-ENC-B") (class "Default")
      (node (ref "P5") (pin "4") (pinfunction "4_4") (pintype "passive"))
      (node (ref "U3") (pin "59") (pinfunction "I1_SDA/T4_C2/PB7_59") (pintype "bidirectional"))
    )
    (net (code "41") (name "/M2-PWM-A") (class "Default")
      (node (ref "R47") (pin "2") (pinfunction "2_2") (pintype "passive"))
      (node (ref "U5") (pin "8") (pinfunction "3Y_8") (pintype "output"))
    )
    (net (code "42") (name "/M2-PWM-B") (class "Default")
      (node (ref "R48") (pin "2") (pinfunction "2_2") (pintype "passive"))
      (node (ref "U5") (pin "11") (pinfunction "4Y_11") (pintype "output"))
    )
    (net (code "43") (name "/M2_PWM") (class "Default")
      (node (ref "U3") (pin "15") (pinfunction "PA1/A12_1/T2_C2/T5_C2_15") (pintype "bidirectional"))
      (node (ref "U5") (pin "12") (pinfunction "4A_12") (pintype "input"))
      (node (ref "U5") (pin "9") (pinfunction "3A_9") (pintype "input"))
    )
    (net (code "44") (name "/MPU6050_RX") (class "Default")
      (node (ref "R33") (pin "1") (pinfunction "1_1") (pintype "passive"))
      (node (ref "U2") (pin "2") (pinfunction "RX_2") (pintype "input"))
      (node (ref "U3") (pin "51") (pinfunction "U4_TX/PC10_51") (pintype "bidirectional"))
    )
    (net (code "45") (name "/MPU6050_TX") (class "Default")
      (node (ref "R34") (pin "1") (pinfunction "1_1") (pintype "passive"))
      (node (ref "U2") (pin "3") (pinfunction "TX_3") (pintype "output"))
      (node (ref "U3") (pin "52") (pinfunction "U4_RX/PC11_52") (pintype "bidirectional"))
    )
    (net (code "46") (name "/NRF_CE") (class "Default")
      (node (ref "J4") (pin "3") (pinfunction "3_3") (pintype "passive"))
      (node (ref "U3") (pin "20") (pinfunction "PA4/A12_4/S1_N_20") (pintype "bidirectional"))
    )
    (net (code "47") (name "/NRF_CSN") (class "Default")
      (node (ref "J4") (pin "4") (pinfunction "4_4") (pintype "passive"))
      (node (ref "U3") (pin "38") (pinfunction "T8_C2/PC7_38") (pintype "bidirectional"))
    )
    (net (code "48") (name "/NRF_IRQ") (class "Default")
      (node (ref "J4") (pin "8") (pinfunction "8_8") (pintype "passive"))
      (node (ref "U3") (pin "39") (pinfunction "T8_C3/PC8_39") (pintype "bidirectional"))
    )
    (net (code "49") (name "/NRF_MISO") (class "Default")
      (node (ref "J4") (pin "7") (pinfunction "7_7") (pintype "passive"))
      (node (ref "R9") (pin "2") (pinfunction "2_2") (pintype "passive"))
      (node (ref "U3") (pin "22") (pinfunction "PA6/A12_6/S1_MI/T3_C1_22") (pintype "bidirectional"))
    )
    (net (code "50") (name "/NRF_MOSI") (class "Default")
      (node (ref "J4") (pin "6") (pinfunction "6_6") (pintype "passive"))
      (node (ref "R11") (pin "2") (pinfunction "2_2") (pintype "passive"))
      (node (ref "U3") (pin "23") (pinfunction "PA7/A12_7/S1_MO/T3_C2_23") (pintype "bidirectional"))
    )
    (net (code "51") (name "/NRF_SCK") (class "Default")
      (node (ref "J4") (pin "5") (pinfunction "5_5") (pintype "passive"))
      (node (ref "R8") (pin "2") (pinfunction "2_2") (pintype "passive"))
      (node (ref "U3") (pin "21") (pinfunction "PA5/A12_5/S1_S_21") (pintype "bidirectional"))
    )
    (net (code "52") (name "/OLED_CS") (class "Default")
      (node (ref "J2") (pin "7") (pinfunction "7_7") (pintype "passive"))
      (node (ref "U3") (pin "33") (pinfunction "S2_NSS/PB12_33") (pintype "bidirectional"))
    )
    (net (code "53") (name "/OLED_D0_SCK") (class "Default")
      (node (ref "J2") (pin "3") (pinfunction "3_3") (pintype "passive"))
      (node (ref "R27") (pin "1") (pinfunction "1_1") (pintype "passive"))
      (node (ref "U3") (pin "34") (pinfunction "S2_SCK/PB13_34") (pintype "bidirectional"))
    )
    (net (code "54") (name "/OLED_D1_MOSI") (class "Default")
      (node (ref "J2") (pin "4") (pinfunction "4_4") (pintype "passive"))
      (node (ref "R28") (pin "1") (pinfunction "1_1") (pintype "passive"))
      (node (ref "U3") (pin "36") (pinfunction "S2_MO/PB15_36") (pintype "bidirectional"))
    )
    (net (code "55") (name "/OLED_DC") (class "Default")
      (node (ref "J2") (pin "6") (pinfunction "6_6") (pintype "passive"))
      (node (ref "U3") (pin "37") (pinfunction "T8_C1/PC6_37") (pintype "bidirectional"))
    )
    (net (code "56") (name "/OLED_RES") (class "Default")
      (node (ref "J2") (pin "5") (pinfunction "5_5") (pintype "passive"))
      (node (ref "U3") (pin "35") (pinfunction "S2_MI/PB14_35") (pintype "bidirectional"))
    )
    (net (code "57") (name "/RST") (class "Default")
      (node (ref "C13") (pin "1") (pinfunction "1_1") (pintype "passive"))
      (node (ref "R7") (pin "2") (pinfunction "2_2") (pintype "passive"))
      (node (ref "S1") (pin "1") (pinfunction "1_1") (pintype "passive"))
      (node (ref "U3") (pin "7") (pinfunction "NRST_7") (pintype "bidirectional"))
    )
    (net (code "58") (name "/RUD1_PWM") (class "Default")
      (node (ref "P7") (pin "3") (pinfunction "3_3") (pintype "passive"))
      (node (ref "U3") (pin "16") (pinfunction "PA2/A12_2/U2_TX/T2_C3/T5_C3_16") (pintype "bidirectional"))
    )
    (net (code "59") (name "/RUD2_PWM") (class "Default")
      (node (ref "P6") (pin "3") (pinfunction "3_3") (pintype "passive"))
      (node (ref "U3") (pin "17") (pinfunction "PA3/A12_3/U2_RX/T2_C4/T5_C4_17") (pintype "bidirectional"))
    )
    (net (code "60") (name "/SWCLK") (class "Default")
      (node (ref "J5") (pin "3") (pinfunction "3_3") (pintype "passive"))
      (node (ref "U3") (pin "49") (pinfunction "PA14/JTCK/SWCLK_49") (pintype "bidirectional"))
    )
    (net (code "61") (name "/SWDIO") (class "Default")
      (node (ref "J5") (pin "2") (pinfunction "2_2") (pintype "passive"))
      (node (ref "U3") (pin "46") (pinfunction "PA13/JTMS/SWDIO_46") (pintype "bidirectional"))
    )
    (net (code "62") (name "/UART1RX") (class "Default")
      (node (ref "J1") (pin "2") (pinfunction "2_2") (pintype "passive"))
      (node (ref "R18") (pin "2") (pinfunction "2_2") (pintype "passive"))
      (node (ref "U3") (pin "43") (pinfunction "PA10/T1_C3/U1_RX_43") (pintype "bidirectional"))
    )
    (net (code "63") (name "/UART1TX") (class "Default")
      (node (ref "J1") (pin "3") (pinfunction "3_3") (pintype "passive"))
      (node (ref "R15") (pin "2") (pinfunction "2_2") (pintype "passive"))
      (node (ref "U3") (pin "42") (pinfunction "PA9__/T1_C2/U1_TX_42") (pintype "bidirectional"))
    )
    (net (code "64") (name "GND") (class "Default")
      (node (ref "C1") (pin "2") (pinfunction "2_2") (pintype "passive"))
      (node (ref "C10") (pin "1") (pinfunction "1_1") (pintype "passive"))
      (node (ref "C11") (pin "2") (pinfunction "2_2") (pintype "passive"))
      (node (ref "C12") (pin "2") (pinfunction "2_2") (pintype "passive"))
      (node (ref "C13") (pin "2") (pinfunction "2_2") (pintype "passive"))
      (node (ref "C16") (pin "1") (pinfunction "1_1") (pintype "passive"))
      (node (ref "C17") (pin "1") (pinfunction "1_1") (pintype "passive"))
      (node (ref "C18") (pin "1") (pinfunction "1_1") (pintype "passive"))
      (node (ref "C19") (pin "1") (pinfunction "1_1") (pintype "passive"))
      (node (ref "C2") (pin "2") (pinfunction "2_2") (pintype "passive"))
      (node (ref "C20") (pin "1") (pinfunction "1_1") (pintype "passive"))
      (node (ref "C22") (pin "1") (pinfunction "1_1") (pintype "passive"))
      (node (ref "C23") (pin "2") (pinfunction "2_2") (pintype "passive"))
      (node (ref "C24") (pin "2") (pinfunction "2_2") (pintype "passive"))
      (node (ref "C25") (pin "2") (pinfunction "2_2") (pintype "passive"))
      (node (ref "C26") (pin "2") (pinfunction "2_2") (pintype "passive"))
      (node (ref "C3") (pin "1") (pinfunction "1_1") (pintype "passive"))
      (node (ref "C4") (pin "2") (pinfunction "2_2") (pintype "passive"))
      (node (ref "C5") (pin "1") (pinfunction "1_1") (pintype "passive"))
      (node (ref "C6") (pin "2") (pinfunction "2_2") (pintype "passive"))
      (node (ref "C7") (pin "2") (pinfunction "2_2") (pintype "passive"))
      (node (ref "C8") (pin "2") (pinfunction "2_2") (pintype "passive"))
      (node (ref "C9") (pin "1") (pinfunction "1_1") (pintype "passive"))
      (node (ref "J1") (pin "4") (pinfunction "4_4") (pintype "passive"))
      (node (ref "J2") (pin "1") (pinfunction "1_1") (pintype "passive"))
      (node (ref "J3") (pin "2") (pinfunction "2_2") (pintype "passive"))
      (node (ref "J4") (pin "1") (pinfunction "1_1") (pintype "passive"))
      (node (ref "J5") (pin "4") (pinfunction "4_4") (pintype "passive"))
      (node (ref "J7") (pin "1") (pinfunction "1_1") (pintype "passive"))
      (node (ref "J8") (pin "2") (pinfunction "2_2") (pintype "passive"))
      (node (ref "J9") (pin "3") (pinfunction "3_3") (pintype "passive"))
      (node (ref "L1") (pin "2") (pinfunction "K_2") (pintype "passive"))
      (node (ref "P1") (pin "1") (pinfunction "1_1") (pintype "passive"))
      (node (ref "P1") (pin "11") (pinfunction "11_11") (pintype "passive"))
      (node (ref "P1") (pin "3") (pinfunction "3_3") (pintype "passive"))
      (node (ref "P1") (pin "5") (pinfunction "5_5") (pintype "passive"))
      (node (ref "P1") (pin "7") (pinfunction "7_7") (pintype "passive"))
      (node (ref "P1") (pin "9") (pinfunction "9_9") (pintype "passive"))
      (node (ref "P2") (pin "1") (pinfunction "1_1") (pintype "passive"))
      (node (ref "P2") (pin "11") (pinfunction "11_11") (pintype "passive"))
      (node (ref "P2") (pin "3") (pinfunction "3_3") (pintype "passive"))
      (node (ref "P2") (pin "5") (pinfunction "5_5") (pintype "passive"))
      (node (ref "P2") (pin "7") (pinfunction "7_7") (pintype "passive"))
      (node (ref "P2") (pin "9") (pinfunction "9_9") (pintype "passive"))
      (node (ref "P4") (pin "5") (pinfunction "5_5") (pintype "passive"))
      (node (ref "P5") (pin "5") (pinfunction "5_5") (pintype "passive"))
      (node (ref "P6") (pin "1") (pinfunction "1_1") (pintype "passive"))
      (node (ref "P7") (pin "1") (pinfunction "1_1") (pintype "passive"))
      (node (ref "Q1") (pin "1") (pinfunction "NS1_1") (pintype "passive"))
      (node (ref "Q2") (pin "1") (pinfunction "NS1_1") (pintype "passive"))
      (node (ref "Q3") (pin "2") (pinfunction "E_2") (pintype "passive"))
      (node (ref "Q4") (pin "2") (pinfunction "E_2") (pintype "passive"))
      (node (ref "Q5") (pin "1") (pinfunction "NS1_1") (pintype "passive"))
      (node (ref "Q6") (pin "1") (pinfunction "NS1_1") (pintype "passive"))
      (node (ref "Q7") (pin "2") (pinfunction "E_2") (pintype "passive"))
      (node (ref "Q8") (pin "2") (pinfunction "E_2") (pintype "passive"))
      (node (ref "R10") (pin "2") (pinfunction "2_2") (pintype "passive"))
      (node (ref "R12") (pin "2") (pinfunction "2_2") (pintype "passive"))
      (node (ref "R2") (pin "1") (pinfunction "1_1") (pintype "passive"))
      (node (ref "R21") (pin "2") (pinfunction "2_2") (pintype "passive"))
      (node (ref "R22") (pin "1") (pinfunction "1_1") (pintype "passive"))
      (node (ref "R26") (pin "2") (pinfunction "2_2") (pintype "passive"))
      (node (ref "R4") (pin "1") (pinfunction "1_1") (pintype "passive"))
      (node (ref "R42") (pin "2") (pinfunction "2_2") (pintype "passive"))
      (node (ref "R43") (pin "2") (pinfunction "2_2") (pintype "passive"))
      (node (ref "R46") (pin "1") (pinfunction "1_1") (pintype "passive"))
      (node (ref "R50") (pin "2") (pinfunction "2_2") (pintype "passive"))
      (node (ref "R51") (pin "2") (pinfunction "2_2") (pintype "passive"))
      (node (ref "R52") (pin "2") (pinfunction "2_2") (pintype "passive"))
      (node (ref "R53") (pin "2") (pinfunction "2_2") (pintype "passive"))
      (node (ref "R54") (pin "2") (pinfunction "2_2") (pintype "passive"))
      (node (ref "S1") (pin "2") (pinfunction "2_2") (pintype "passive"))
      (node (ref "U1") (pin "2") (pinfunction "GND_2") (pintype "passive"))
      (node (ref "U2") (pin "4") (pinfunction "GND_4") (pintype "power_in"))
      (node (ref "U2") (pin "8") (pinfunction "GND2_8") (pintype "passive"))
      (node (ref "U3") (pin "12") (pinfunction "VSSA_12") (pintype "power_in"))
      (node (ref "U3") (pin "18") (pinfunction "VSS_4_18") (pintype "power_in"))
      (node (ref "U3") (pin "31") (pinfunction "VSS_1_31") (pintype "power_in"))
      (node (ref "U3") (pin "47") (pinfunction "VSS_2_47") (pintype "power_in"))
      (node (ref "U3") (pin "63") (pinfunction "VSS_3_63") (pintype "power_in"))
      (node (ref "U4") (pin "11") (pinfunction "5A_11") (pintype "input"))
      (node (ref "U4") (pin "13") (pinfunction "6A_13") (pintype "input"))
      (node (ref "U4") (pin "5") (pinfunction "3A_5") (pintype "input"))
      (node (ref "U4") (pin "7") (pinfunction "GND_7") (pintype "power_in"))
      (node (ref "U4") (pin "9") (pinfunction "4A_9") (pintype "input"))
      (node (ref "U5") (pin "7") (pinfunction "GND_7") (pintype "power_in"))
    )
    (net (code "65") (name "Net-(D1-K)") (class "Default")
      (node (ref "C5") (pin "2") (pinfunction "2_2") (pintype "passive"))
      (node (ref "D1") (pin "2") (pinfunction "K_2") (pintype "passive"))
      (node (ref "U1") (pin "1") (pinfunction "VIN_1") (pintype "passive"))
      (node (ref "U1") (pin "3") (pinfunction "CE_3") (pintype "passive"))
    )
    (net (code "66") (name "Net-(J1-Pad1)") (class "Default")
      (node (ref "J1") (pin "1") (pinfunction "1_1") (pintype "passive"))
      (node (ref "J6") (pin "2") (pinfunction "2_2") (pintype "passive"))
    )
    (net (code "67") (name "Net-(J7-Pad2)") (class "Default")
      (node (ref "J7") (pin "2") (pinfunction "2_2") (pintype "passive"))
      (node (ref "S2") (pin "2") (pinfunction "2_2") (pintype "passive"))
    )
    (net (code "68") (name "Net-(L1-A)") (class "Default")
      (node (ref "L1") (pin "1") (pinfunction "A_1") (pintype "passive"))
      (node (ref "R1") (pin "1") (pinfunction "1_1") (pintype "passive"))
    )
    (net (code "69") (name "Net-(LED1-Pad2)") (class "Default")
      (node (ref "LED1") (pin "2") (pinfunction "2_2") (pintype "passive"))
      (node (ref "R51") (pin "1") (pinfunction "1_1") (pintype "passive"))
    )
    (net (code "70") (name "Net-(LED2-Pad2)") (class "Default")
      (node (ref "LED2") (pin "2") (pinfunction "2_2") (pintype "passive"))
      (node (ref "R52") (pin "1") (pinfunction "1_1") (pintype "passive"))
    )
    (net (code "71") (name "Net-(LED3-Pad2)") (class "Default")
      (node (ref "LED3") (pin "2") (pinfunction "2_2") (pintype "passive"))
      (node (ref "R53") (pin "1") (pinfunction "1_1") (pintype "passive"))
    )
    (net (code "72") (name "Net-(LED4-Pad2)") (class "Default")
      (node (ref "LED4") (pin "2") (pinfunction "2_2") (pintype "passive"))
      (node (ref "R54") (pin "1") (pinfunction "1_1") (pintype "passive"))
    )
    (net (code "73") (name "Net-(P8-Pad2)") (class "Default")
      (node (ref "P8") (pin "2") (pinfunction "2_2") (pintype "passive"))
      (node (ref "R3") (pin "1") (pinfunction "1_1") (pintype "passive"))
    )
    (net (code "74") (name "Net-(P9-Pad2)") (class "Default")
      (node (ref "P9") (pin "2") (pinfunction "2_2") (pintype "passive"))
      (node (ref "R30") (pin "1") (pinfunction "1_1") (pintype "passive"))
    )
    (net (code "75") (name "Net-(Q1-NG1)") (class "Default")
      (node (ref "Q1") (pin "2") (pinfunction "NG1_2") (pintype "passive"))
      (node (ref "R12") (pin "1") (pinfunction "1_1") (pintype "passive"))
      (node (ref "R23") (pin "1") (pinfunction "1_1") (pintype "passive"))
    )
    (net (code "76") (name "Net-(Q1-PG2)") (class "Default")
      (node (ref "Q1") (pin "4") (pinfunction "PG2_4") (pintype "passive"))
      (node (ref "Q3") (pin "3") (pinfunction "C_3") (pintype "passive"))
      (node (ref "R5") (pin "1") (pinfunction "1_1") (pintype "passive"))
    )
    (net (code "77") (name "Net-(Q2-NG1)") (class "Default")
      (node (ref "Q2") (pin "2") (pinfunction "NG1_2") (pintype "passive"))
      (node (ref "R10") (pin "1") (pinfunction "1_1") (pintype "passive"))
      (node (ref "R24") (pin "1") (pinfunction "1_1") (pintype "passive"))
    )
    (net (code "78") (name "Net-(Q2-PG2)") (class "Default")
      (node (ref "Q2") (pin "4") (pinfunction "PG2_4") (pintype "passive"))
      (node (ref "Q4") (pin "3") (pinfunction "C_3") (pintype "passive"))
      (node (ref "R6") (pin "1") (pinfunction "1_1") (pintype "passive"))
    )
    (net (code "79") (name "Net-(Q3-B)") (class "Default")
      (node (ref "Q3") (pin "1") (pinfunction "B_1") (pintype "passive"))
      (node (ref "R17") (pin "1") (pinfunction "1_1") (pintype "passive"))
      (node (ref "R22") (pin "2") (pinfunction "2_2") (pintype "passive"))
    )
    (net (code "80") (name "Net-(Q4-B)") (class "Default")
      (node (ref "Q4") (pin "1") (pinfunction "B_1") (pintype "passive"))
      (node (ref "R14") (pin "2") (pinfunction "2_2") (pintype "passive"))
      (node (ref "R26") (pin "1") (pinfunction "1_1") (pintype "passive"))
    )
    (net (code "81") (name "Net-(Q5-NG1)") (class "Default")
      (node (ref "Q5") (pin "2") (pinfunction "NG1_2") (pintype "passive"))
      (node (ref "R43") (pin "1") (pinfunction "1_1") (pintype "passive"))
      (node (ref "R47") (pin "1") (pinfunction "1_1") (pintype "passive"))
    )
    (net (code "82") (name "Net-(Q5-PG2)") (class "Default")
      (node (ref "Q5") (pin "4") (pinfunction "PG2_4") (pintype "passive"))
      (node (ref "Q7") (pin "3") (pinfunction "C_3") (pintype "passive"))
      (node (ref "R35") (pin "1") (pinfunction "1_1") (pintype "passive"))
    )
    (net (code "83") (name "Net-(Q6-NG1)") (class "Default")
      (node (ref "Q6") (pin "2") (pinfunction "NG1_2") (pintype "passive"))
      (node (ref "R42") (pin "1") (pinfunction "1_1") (pintype "passive"))
      (node (ref "R48") (pin "1") (pinfunction "1_1") (pintype "passive"))
    )
    (net (code "84") (name "Net-(Q6-PG2)") (class "Default")
      (node (ref "Q6") (pin "4") (pinfunction "PG2_4") (pintype "passive"))
      (node (ref "Q8") (pin "3") (pinfunction "C_3") (pintype "passive"))
      (node (ref "R36") (pin "1") (pinfunction "1_1") (pintype "passive"))
    )
    (net (code "85") (name "Net-(Q7-B)") (class "Default")
      (node (ref "Q7") (pin "1") (pinfunction "B_1") (pintype "passive"))
      (node (ref "R45") (pin "1") (pinfunction "1_1") (pintype "passive"))
      (node (ref "R46") (pin "2") (pinfunction "2_2") (pintype "passive"))
    )
    (net (code "86") (name "Net-(Q8-B)") (class "Default")
      (node (ref "Q8") (pin "1") (pinfunction "B_1") (pintype "passive"))
      (node (ref "R44") (pin "2") (pinfunction "2_2") (pintype "passive"))
      (node (ref "R50") (pin "1") (pinfunction "1_1") (pintype "passive"))
    )
    (net (code "87") (name "Net-(U3-OSC_IN{slash}PD0)") (class "Default")
      (node (ref "C16") (pin "2") (pinfunction "2_2") (pintype "passive"))
      (node (ref "U3") (pin "5") (pinfunction "OSC_IN/PD0_5") (pintype "input"))
      (node (ref "X1") (pin "2") (pinfunction "2_2") (pintype "passive"))
    )
    (net (code "88") (name "Net-(U3-OSC_OUT{slash}PD1)") (class "Default")
      (node (ref "C17") (pin "2") (pinfunction "2_2") (pintype "passive"))
      (node (ref "U3") (pin "6") (pinfunction "OSC_OUT/PD1_6") (pintype "output"))
      (node (ref "X1") (pin "1") (pinfunction "1_1") (pintype "passive"))
    )
    (net (code "89") (name "Net-(U3-VBAT)") (class "Default")
      (node (ref "R40") (pin "2") (pinfunction "2_2") (pintype "passive"))
      (node (ref "U3") (pin "1") (pinfunction "VBAT_1") (pintype "power_in"))
    )
    (net (code "90") (name "VCC-3.3V") (class "Default")
      (node (ref "C1") (pin "1") (pinfunction "1_1") (pintype "passive"))
      (node (ref "C10") (pin "2") (pinfunction "2_2") (pintype "passive"))
      (node (ref "C18") (pin "2") (pinfunction "2_2") (pintype "passive"))
      (node (ref "C19") (pin "2") (pinfunction "2_2") (pintype "passive"))
      (node (ref "C2") (pin "1") (pinfunction "1_1") (pintype "passive"))
      (node (ref "C20") (pin "2") (pinfunction "2_2") (pintype "passive"))
      (node (ref "C24") (pin "1") (pinfunction "1_1") (pintype "passive"))
      (node (ref "C26") (pin "1") (pinfunction "1_1") (pintype "passive"))
      (node (ref "C3") (pin "2") (pinfunction "2_2") (pintype "passive"))
      (node (ref "C4") (pin "1") (pinfunction "1_1") (pintype "passive"))
      (node (ref "C6") (pin "1") (pinfunction "1_1") (pintype "passive"))
      (node (ref "C7") (pin "1") (pinfunction "1_1") (pintype "passive"))
      (node (ref "C8") (pin "1") (pinfunction "1_1") (pintype "passive"))
      (node (ref "C9") (pin "2") (pinfunction "2_2") (pintype "passive"))
      (node (ref "J2") (pin "2") (pinfunction "2_2") (pintype "passive"))
      (node (ref "J3") (pin "1") (pinfunction "1_1") (pintype "passive"))
      (node (ref "J4") (pin "2") (pinfunction "2_2") (pintype "passive"))
      (node (ref "J5") (pin "1") (pinfunction "1_1") (pintype "passive"))
      (node (ref "J8") (pin "7") (pinfunction "7_7") (pintype "passive"))
      (node (ref "P2") (pin "10") (pinfunction "10_10") (pintype "passive"))
      (node (ref "P2") (pin "12") (pinfunction "12_12") (pintype "passive"))
      (node (ref "P2") (pin "2") (pinfunction "2_2") (pintype "passive"))
      (node (ref "P2") (pin "4") (pinfunction "4_4") (pintype "passive"))
      (node (ref "P2") (pin "6") (pinfunction "6_6") (pintype "passive"))
      (node (ref "P2") (pin "8") (pinfunction "8_8") (pintype "passive"))
      (node (ref "R1") (pin "2") (pinfunction "2_2") (pintype "passive"))
      (node (ref "R11") (pin "1") (pinfunction "1_1") (pintype "passive"))
      (node (ref "R13") (pin "2") (pinfunction "2_2") (pintype "passive"))
      (node (ref "R15") (pin "1") (pinfunction "1_1") (pintype "passive"))
      (node (ref "R16") (pin "2") (pinfunction "2_2") (pintype "passive"))
      (node (ref "R18") (pin "1") (pinfunction "1_1") (pintype "passive"))
      (node (ref "R19") (pin "2") (pinfunction "2_2") (pintype "passive"))
      (node (ref "R2") (pin "2") (pinfunction "2_2") (pintype "passive"))
      (node (ref "R20") (pin "2") (pinfunction "2_2") (pintype "passive"))
      (node (ref "R27") (pin "2") (pinfunction "2_2") (pintype "passive"))
      (node (ref "R28") (pin "2") (pinfunction "2_2") (pintype "passive"))
      (node (ref "R29") (pin "1") (pinfunction "1_1") (pintype "passive"))
      (node (ref "R3") (pin "2") (pinfunction "2_2") (pintype "passive"))
      (node (ref "R30") (pin "2") (pinfunction "2_2") (pintype "passive"))
      (node (ref "R32") (pin "2") (pinfunction "2_2") (pintype "passive"))
      (node (ref "R33") (pin "2") (pinfunction "2_2") (pintype "passive"))
      (node (ref "R34") (pin "2") (pinfunction "2_2") (pintype "passive"))
      (node (ref "R37") (pin "2") (pinfunction "2_2") (pintype "passive"))
      (node (ref "R38") (pin "2") (pinfunction "2_2") (pintype "passive"))
      (node (ref "R39") (pin "2") (pinfunction "2_2") (pintype "passive"))
      (node (ref "R40") (pin "1") (pinfunction "1_1") (pintype "passive"))
      (node (ref "R41") (pin "2") (pinfunction "2_2") (pintype "passive"))
      (node (ref "R7") (pin "1") (pinfunction "1_1") (pintype "passive"))
      (node (ref "R8") (pin "1") (pinfunction "1_1") (pintype "passive"))
      (node (ref "R9") (pin "1") (pinfunction "1_1") (pintype "passive"))
      (node (ref "U1") (pin "5") (pinfunction "OUT_5") (pintype "passive"))
      (node (ref "U2") (pin "1") (pinfunction "VCC_1") (pintype "power_in"))
      (node (ref "U3") (pin "13") (pinfunction "VDDA_13") (pintype "power_in"))
      (node (ref "U3") (pin "19") (pinfunction "VDD_4_19") (pintype "power_in"))
      (node (ref "U3") (pin "32") (pinfunction "VDD_1_32") (pintype "power_in"))
      (node (ref "U3") (pin "48") (pinfunction "VDD_2_48") (pintype "power_in"))
      (node (ref "U3") (pin "64") (pinfunction "VDD_3_64") (pintype "power_in"))
    )
    (net (code "91") (name "VCC-5V") (class "Default")
      (node (ref "C11") (pin "1") (pinfunction "1_1") (pintype "passive"))
      (node (ref "C12") (pin "1") (pinfunction "1_1") (pintype "passive"))
      (node (ref "C22") (pin "2") (pinfunction "2_2") (pintype "passive"))
      (node (ref "C23") (pin "1") (pinfunction "1_1") (pintype "passive"))
      (node (ref "C25") (pin "1") (pinfunction "1_1") (pintype "passive"))
      (node (ref "D1") (pin "1") (pinfunction "A_1") (pintype "passive"))
      (node (ref "J6") (pin "1") (pinfunction "1_1") (pintype "passive"))
      (node (ref "J9") (pin "2") (pinfunction "2_2") (pintype "passive"))
      (node (ref "P1") (pin "10") (pinfunction "10_10") (pintype "passive"))
      (node (ref "P1") (pin "12") (pinfunction "12_12") (pintype "passive"))
      (node (ref "P1") (pin "2") (pinfunction "2_2") (pintype "passive"))
      (node (ref "P1") (pin "4") (pinfunction "4_4") (pintype "passive"))
      (node (ref "P1") (pin "6") (pinfunction "6_6") (pintype "passive"))
      (node (ref "P1") (pin "8") (pinfunction "8_8") (pintype "passive"))
      (node (ref "P4") (pin "2") (pinfunction "2_2") (pintype "passive"))
      (node (ref "P5") (pin "2") (pinfunction "2_2") (pintype "passive"))
      (node (ref "P6") (pin "2") (pinfunction "2_2") (pintype "passive"))
      (node (ref "P7") (pin "2") (pinfunction "2_2") (pintype "passive"))
      (node (ref "Q1") (pin "3") (pinfunction "PS2_3") (pintype "passive"))
      (node (ref "Q2") (pin "3") (pinfunction "PS2_3") (pintype "passive"))
      (node (ref "Q5") (pin "3") (pinfunction "PS2_3") (pintype "passive"))
      (node (ref "Q6") (pin "3") (pinfunction "PS2_3") (pintype "passive"))
      (node (ref "R35") (pin "2") (pinfunction "2_2") (pintype "passive"))
      (node (ref "R36") (pin "2") (pinfunction "2_2") (pintype "passive"))
      (node (ref "R4") (pin "2") (pinfunction "2_2") (pintype "passive"))
      (node (ref "R5") (pin "2") (pinfunction "2_2") (pintype "passive"))
      (node (ref "R6") (pin "2") (pinfunction "2_2") (pintype "passive"))
      (node (ref "S2") (pin "1") (pinfunction "1_1") (pintype "passive"))
      (node (ref "U4") (pin "14") (pinfunction "VCC_14") (pintype "power_in"))
      (node (ref "U5") (pin "14") (pinfunction "VCC_14") (pintype "power_in"))
    )
    (net (code "92") (name "unconnected-(S2-Pad3)") (class "Default")
      (node (ref "S2") (pin "3") (pinfunction "3_3") (pintype "passive"))
    )
    (net (code "93") (name "unconnected-(U1-NC-Pad4)") (class "Default")
      (node (ref "U1") (pin "4") (pinfunction "NC_4") (pintype "passive"))
    )
    (net (code "94") (name "unconnected-(U2-SCL-Pad6)") (class "Default")
      (node (ref "U2") (pin "6") (pinfunction "SCL_6") (pintype "input+no_connect"))
    )
    (net (code "95") (name "unconnected-(U2-SDA-Pad7)") (class "Default")
      (node (ref "U2") (pin "7") (pinfunction "SDA_7") (pintype "bidirectional+no_connect"))
    )
    (net (code "96") (name "unconnected-(U2-VCC-Pad5)") (class "Default")
      (node (ref "U2") (pin "5") (pinfunction "VCC_5") (pintype "power_in+no_connect"))
    )
    (net (code "97") (name "unconnected-(U4-3Y-Pad6)") (class "Default")
      (node (ref "U4") (pin "6") (pinfunction "3Y_6") (pintype "output"))
    )
    (net (code "98") (name "unconnected-(U4-4Y-Pad8)") (class "Default")
      (node (ref "U4") (pin "8") (pinfunction "4Y_8") (pintype "output"))
    )
    (net (code "99") (name "unconnected-(U4-5Y-Pad10)") (class "Default")
      (node (ref "U4") (pin "10") (pinfunction "5Y_10") (pintype "output"))
    )
    (net (code "100") (name "unconnected-(U4-6Y-Pad12)") (class "Default")
      (node (ref "U4") (pin "12") (pinfunction "6Y_12") (pintype "output"))
    )
  )
)
